# Config_Clock.net
KiCad netlist of a schematic drawn in Altium Designer
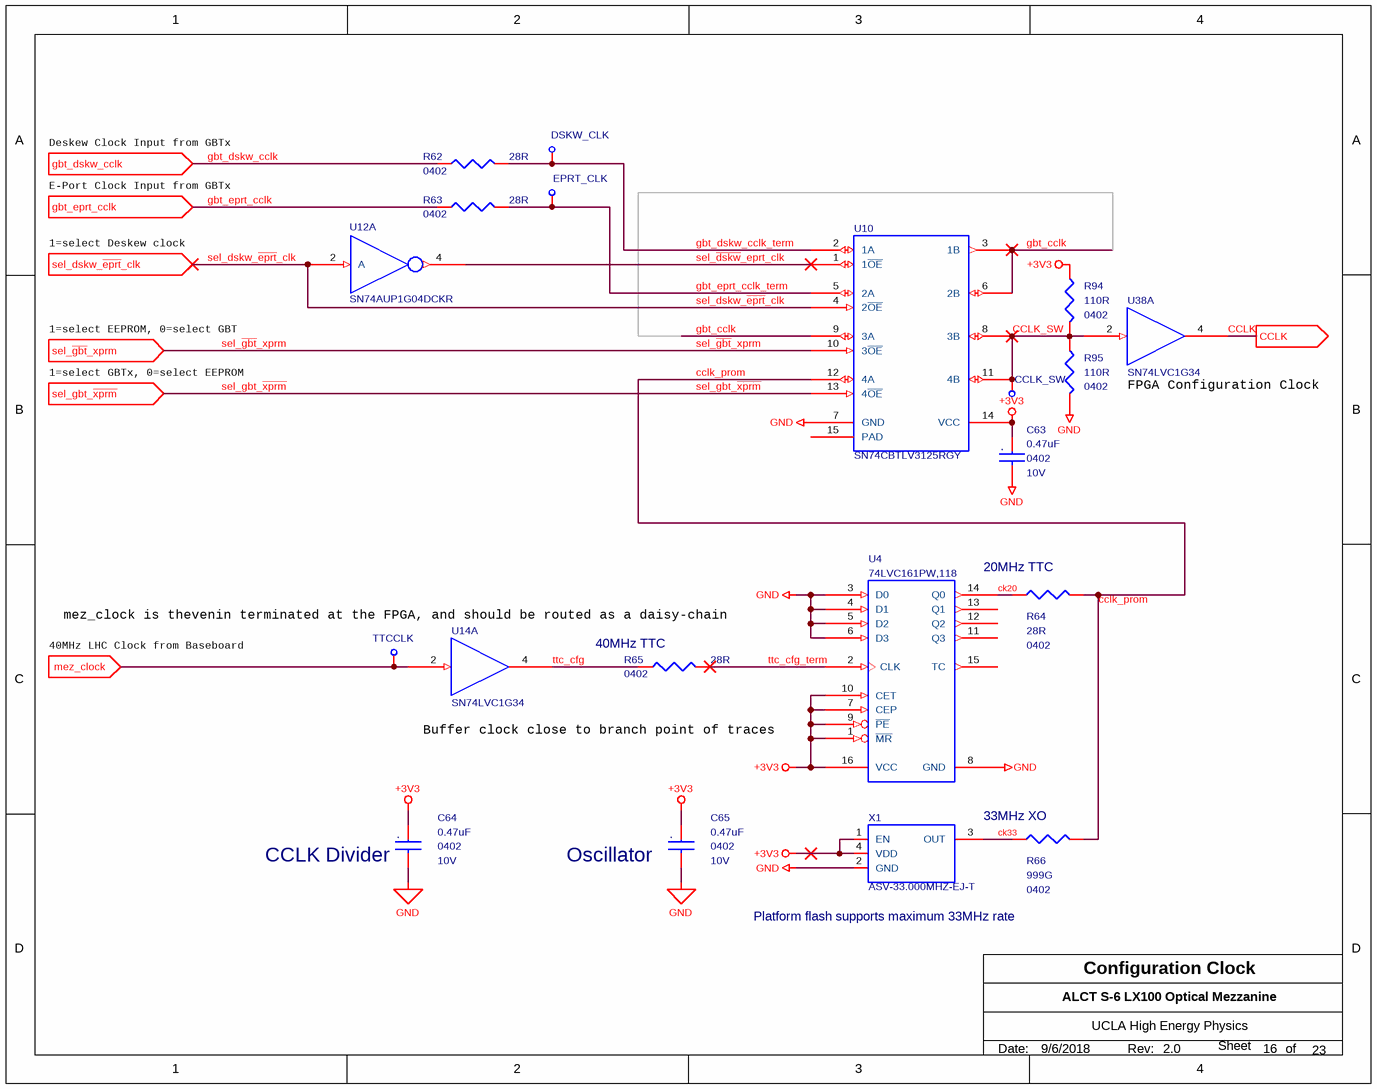
[diagram p0: Config_Clock.SchDoc]

(export (version "E")
  (design (tool "Eeschema 10.0.6"))
  (components
    (comp (ref "C63")
      (value "0.47uF")
      (footprint "MC_S6/SM/C_0402_IPC")
      (description "CAP CER 0.47UF 10V X5R 0402")
      (fields
        (field (name "MANUFACTURER") "Murata Electronics North America")
        (field (name "MANUFACTURER PART NUMBER") "GRM155R61A474KE15D")
        (field (name "VOLTAGE - RATED") "10V")
        (field (name "PACKAGE") "0402")
      )
      (libsource (lib "ALCT_MEZ_SPARTAN6_Library") (part "GRM155R61A474KE15D"))
    )
    (comp (ref "C64")
      (value "0.47uF")
      (footprint "MC_S6/SM/C_0402_IPC")
      (description "CAP CER 0.47UF 10V X5R 0402")
      (fields
        (field (name "MANUFACTURER") "Murata Electronics North America")
        (field (name "MANUFACTURER PART NUMBER") "GRM155R61A474KE15D")
        (field (name "PACKAGE") "0402")
        (field (name "VOLTAGE - RATED") "10V")
      )
      (libsource (lib "ALCT_MEZ_SPARTAN6_Library") (part "GRM155R61A474KE15D"))
    )
    (comp (ref "C65")
      (value "0.47uF")
      (footprint "MC_S6/SM/C_0402_IPC")
      (description "CAP CER 0.47UF 10V X5R 0402")
      (fields
        (field (name "MANUFACTURER") "Murata Electronics North America")
        (field (name "MANUFACTURER PART NUMBER") "GRM155R61A474KE15D")
        (field (name "PACKAGE") "0402")
        (field (name "VOLTAGE - RATED") "10V")
      )
      (libsource (lib "ALCT_MEZ_SPARTAN6_Library") (part "GRM155R61A474KE15D"))
    )
    (comp (ref "CCLK_SW")
      (value "Test Point Via")
      (footprint "MC_S6/TH/TPVIA")
      (libsource (lib "ALCT_MEZ_SPARTAN6_Library") (part "TPVIA"))
    )
    (comp (ref "DSKW_CLK")
      (value "Test Point Via")
      (footprint "MC_S6/TH/TPVIA")
      (libsource (lib "ALCT_MEZ_SPARTAN6_Library") (part "TPVIA"))
    )
    (comp (ref "EPRT_CLK")
      (value "Test Point Via")
      (footprint "MC_S6/TH/TPVIA")
      (libsource (lib "ALCT_MEZ_SPARTAN6_Library") (part "TPVIA"))
    )
    (comp (ref "R62")
      (value "28R")
      (footprint "MC_S6/SM/R_0402_IPC")
      (description "RES SMD 28 OHM 1% 1/10W 0402")
      (fields
        (field (name "TOLERANCE") "±1%")
        (field (name "MANUFACTURER") "Panasonic Electronic Components")
        (field (name "SUPPLIER DEVICE PACKAGE") "0402")
      )
      (libsource (lib "ALCT_MEZ_SPARTAN6_Library") (part "ERJ-2RKF28R0X"))
    )
    (comp (ref "R63")
      (value "28R")
      (footprint "MC_S6/SM/R_0402_IPC")
      (description "RES SMD 28 OHM 1% 1/10W 0402")
      (fields
        (field (name "TOLERANCE") "±1%")
        (field (name "MANUFACTURER") "Panasonic Electronic Components")
        (field (name "SUPPLIER DEVICE PACKAGE") "0402")
      )
      (libsource (lib "ALCT_MEZ_SPARTAN6_Library") (part "ERJ-2RKF28R0X"))
    )
    (comp (ref "R64")
      (value "28R")
      (footprint "MC_S6/SM/R_0402_IPC")
      (description "RES SMD 28 OHM 1% 1/10W 0402")
      (fields
        (field (name "TOLERANCE") "±1%")
        (field (name "MANUFACTURER") "Panasonic Electronic Components")
        (field (name "SUPPLIER DEVICE PACKAGE") "0402")
      )
      (libsource (lib "ALCT_MEZ_SPARTAN6_Library") (part "ERJ-2RKF28R0X"))
    )
    (comp (ref "R65")
      (value "28R")
      (footprint "MC_S6/SM/R_0402_IPC")
      (description "RES SMD 28 OHM 1% 1/10W 0402")
      (fields
        (field (name "TOLERANCE") "±1%")
        (field (name "MANUFACTURER") "Panasonic Electronic Components")
        (field (name "SUPPLIER DEVICE PACKAGE") "0402")
      )
      (libsource (lib "ALCT_MEZ_SPARTAN6_Library") (part "ERJ-2RKF28R0X"))
    )
    (comp (ref "R66")
      (value "999G")
      (footprint "MC_S6/SM/R_0402_IPC")
      (description "RES SMD 999G OHM 5% 1/16W 0402")
      (fields
        (field (name "SUPPLIER DEVICE PACKAGE") "0402")
        (field (name "MANUFACTURER PART NUMBER") "Do Not Place")
      )
      (libsource (lib "ALCT_MEZ_SPARTAN6_Library") (part "RES999G 0402"))
    )
    (comp (ref "R94")
      (value "110R")
      (footprint "MC_S6/SM/R_0402_IPC")
      (description "RES SMD 110 OHM 1% 1/10W 0402")
      (fields
        (field (name "MANUFACTURER") "Panasonic Electronic Components")
        (field (name "MANUFACTURER PART NUMBER") "ERJ-2RKF1100X")
        (field (name "SUPPLIER DEVICE PACKAGE") "0402")
      )
      (libsource (lib "ALCT_MEZ_SPARTAN6_Library") (part "ERJ-2RKF1100X"))
    )
    (comp (ref "R95")
      (value "110R")
      (footprint "MC_S6/SM/R_0402_IPC")
      (description "RES SMD 110 OHM 1% 1/10W 0402")
      (fields
        (field (name "MANUFACTURER") "Panasonic Electronic Components")
        (field (name "MANUFACTURER PART NUMBER") "ERJ-2RKF1100X")
        (field (name "SUPPLIER DEVICE PACKAGE") "0402")
      )
      (libsource (lib "ALCT_MEZ_SPARTAN6_Library") (part "ERJ-2RKF1100X"))
    )
    (comp (ref "TTCCLK")
      (value "Test Point Via")
      (footprint "MC_S6/TH/TPVIA")
      (libsource (lib "ALCT_MEZ_SPARTAN6_Library") (part "TPVIA"))
    )
    (comp (ref "U4")
      (value "74LVC161PW,118")
      (footprint "MC_S6/SM/TSSOP16")
      (description "IC SYNC 4BIT BIN COUNTER 16TSSOP")
      (fields (field (name "MANUFACTURER") "NXP USA Inc."))
      (libsource (lib "ALCT_MEZ_SPARTAN6_Library") (part "74LVC161PW"))
    )
    (comp (ref "U10")
      (value "SN74CBTLV3125RGY")
      (footprint "S-PVQFN-N14")
      (description "IC 4 BIT FET BUS SWITCH, QFN-14")
      (fields
        (field (name "MANUFACTURER") "Texas Instruments")
        (field (name "MANUFACTURER PART NUMBER") "SN74CBTLV3125RGYR")
      )
      (libsource (lib "ALCT_MEZ_SPARTAN6_Library") (part "SN74CBTLV3125RGY"))
    )
    (comp (ref "U12")
      (value "SN74AUP1G04DCKR")
      (footprint "MC_S6/SM/SOT_SC70_DCK5")
      (description "IC INVERTER LP 5TSSOP")
      (fields (field (name "MANUFACTURER") "Texas Instruments"))
      (libsource (lib "ALCT_MEZ_SPARTAN6_Library") (part "SN74AUP1G04DCKR"))
    )
    (comp (ref "U14")
      (value "SN74LVC1G34")
      (footprint "MC_S6/SM/SOT_553_DRL5")
      (description "IC BUFFER NON-INVERT SOT5")
      (fields
        (field (name "MANUFACTURER") "Texas Instruments")
        (field (name "MANUFACTURER PART NUMBER") "SN74LVC1G34DRLR")
      )
      (libsource (lib "ALCT_MEZ_SPARTAN6_Library") (part "SN74LVC1G34DRLR"))
    )
    (comp (ref "U38")
      (value "SN74LVC1G34")
      (footprint "MC_S6/SM/SOT_553_DRL5")
      (description "IC BUFFER NON-INVERT SOT5")
      (fields
        (field (name "MANUFACTURER") "Texas Instruments")
        (field (name "MANUFACTURER PART NUMBER") "SN74LVC1G34DRLR")
      )
      (libsource (lib "ALCT_MEZ_SPARTAN6_Library") (part "SN74LVC1G34DRLR"))
    )
    (comp (ref "X1")
      (value "ASV-33.000MHZ-EJ-T")
      (footprint "MC_S6/SM/XTAL-7x5.08")
      (description "XTAL, 33MHz, CMOS")
      (fields (field (name "MANUFACTURER") "Abracon LLC"))
      (libsource (lib "ALCT_MEZ_SPARTAN6_Library") (part "ASV-33.000MHZ-EJ-T"))
    )
  )
  (nets
    (net (code "1") (name "+3V3") (class "Default")
      (node (ref "C63") (pin "1") (pinfunction "1_1") (pintype "passive"))
      (node (ref "C64") (pin "1") (pinfunction "1_1") (pintype "passive"))
      (node (ref "C65") (pin "1") (pinfunction "1_1") (pintype "passive"))
      (node (ref "R94") (pin "1") (pinfunction "1_1") (pintype "passive"))
      (node (ref "U10") (pin "14") (pinfunction "VCC_14") (pintype "power_in"))
      (node (ref "U4") (pin "1") (pinfunction "~{MR}_1") (pintype "input"))
      (node (ref "U4") (pin "10") (pinfunction "CET_10") (pintype "input"))
      (node (ref "U4") (pin "16") (pinfunction "VCC_16") (pintype "power_in"))
      (node (ref "U4") (pin "7") (pinfunction "CEP_7") (pintype "input"))
      (node (ref "U4") (pin "9") (pinfunction "~{PE}_9") (pintype "input"))
      (node (ref "X1") (pin "1") (pinfunction "EN_1") (pintype "passive"))
      (node (ref "X1") (pin "4") (pinfunction "VDD_4") (pintype "passive"))
    )
    (net (code "2") (name "/CCLK") (class "Default")
      (node (ref "U38") (pin "4") (pinfunction "Y_4") (pintype "open_collector"))
    )
    (net (code "3") (name "/CCLK_SW") (class "Default")
      (node (ref "CCLK_SW") (pin "1") (pinfunction "In_1") (pintype "passive"))
      (node (ref "R94") (pin "2") (pinfunction "2_2") (pintype "passive"))
      (node (ref "R95") (pin "1") (pinfunction "1_1") (pintype "passive"))
      (node (ref "U10") (pin "11") (pinfunction "4B_11") (pintype "bidirectional"))
      (node (ref "U10") (pin "8") (pinfunction "3B_8") (pintype "bidirectional"))
      (node (ref "U38") (pin "2") (pinfunction "A_2") (pintype "input"))
    )
    (net (code "4") (name "/cclk_prom") (class "Default")
      (node (ref "R64") (pin "2") (pinfunction "2_2") (pintype "passive"))
      (node (ref "R66") (pin "2") (pinfunction "2_2") (pintype "passive"))
      (node (ref "U10") (pin "12") (pinfunction "4A_12") (pintype "bidirectional"))
    )
    (net (code "5") (name "/ck20") (class "Default")
      (node (ref "R64") (pin "1") (pinfunction "1_1") (pintype "passive"))
      (node (ref "U4") (pin "14") (pinfunction "Q0_14") (pintype "output"))
    )
    (net (code "6") (name "/ck33") (class "Default")
      (node (ref "R66") (pin "1") (pinfunction "1_1") (pintype "passive"))
      (node (ref "X1") (pin "3") (pinfunction "OUT_3") (pintype "passive"))
    )
    (net (code "7") (name "/gbt_cclk") (class "Default")
      (node (ref "U10") (pin "3") (pinfunction "1B_3") (pintype "output"))
      (node (ref "U10") (pin "6") (pinfunction "2B_6") (pintype "bidirectional"))
      (node (ref "U10") (pin "9") (pinfunction "3A_9") (pintype "bidirectional"))
    )
    (net (code "8") (name "/gbt_dskw_cclk") (class "Default")
      (node (ref "R62") (pin "1") (pinfunction "1_1") (pintype "passive"))
    )
    (net (code "9") (name "/gbt_dskw_cclk_term") (class "Default")
      (node (ref "DSKW_CLK") (pin "1") (pinfunction "In_1") (pintype "passive"))
      (node (ref "R62") (pin "2") (pinfunction "2_2") (pintype "passive"))
      (node (ref "U10") (pin "2") (pinfunction "1A_2") (pintype "bidirectional"))
    )
    (net (code "10") (name "/gbt_eprt_cclk") (class "Default")
      (node (ref "R63") (pin "1") (pinfunction "1_1") (pintype "passive"))
    )
    (net (code "11") (name "/gbt_eprt_cclk_term") (class "Default")
      (node (ref "EPRT_CLK") (pin "1") (pinfunction "In_1") (pintype "passive"))
      (node (ref "R63") (pin "2") (pinfunction "2_2") (pintype "passive"))
      (node (ref "U10") (pin "5") (pinfunction "2A_5") (pintype "bidirectional"))
    )
    (net (code "12") (name "/mez_clock") (class "Default")
      (node (ref "TTCCLK") (pin "1") (pinfunction "In_1") (pintype "passive"))
      (node (ref "U14") (pin "2") (pinfunction "A_2") (pintype "input"))
    )
    (net (code "13") (name "/sel_dskw_~{eprt}_clk") (class "Default")
      (node (ref "U10") (pin "4") (pinfunction "2~{OE}_4") (pintype "input"))
      (node (ref "U12") (pin "2") (pinfunction "A_2") (pintype "input"))
    )
    (net (code "14") (name "/sel_gbt_~{xprm}") (class "Default")
      (node (ref "U10") (pin "13") (pinfunction "4~{OE}_13") (pintype "input"))
    )
    (net (code "15") (name "/sel_~{dskw}_eprt_clk") (class "Default")
      (node (ref "U10") (pin "1") (pinfunction "1~{OE}_1") (pintype "bidirectional"))
      (node (ref "U12") (pin "4") (pinfunction "Y_4") (pintype "output"))
    )
    (net (code "16") (name "/sel_~{gbt}_xprm") (class "Default")
      (node (ref "U10") (pin "10") (pinfunction "3~{OE}_10") (pintype "input"))
    )
    (net (code "17") (name "/ttc_cfg") (class "Default")
      (node (ref "R65") (pin "1") (pinfunction "1_1") (pintype "passive"))
      (node (ref "U14") (pin "4") (pinfunction "Y_4") (pintype "open_collector"))
    )
    (net (code "18") (name "/ttc_cfg_term") (class "Default")
      (node (ref "R65") (pin "2") (pinfunction "2_2") (pintype "passive"))
      (node (ref "U4") (pin "2") (pinfunction "CLK_2") (pintype "input"))
    )
    (net (code "19") (name "GND") (class "Default")
      (node (ref "C63") (pin "2") (pinfunction "2_2") (pintype "passive"))
      (node (ref "C64") (pin "2") (pinfunction "2_2") (pintype "passive"))
      (node (ref "C65") (pin "2") (pinfunction "2_2") (pintype "passive"))
      (node (ref "R95") (pin "2") (pinfunction "2_2") (pintype "passive"))
      (node (ref "U10") (pin "7") (pinfunction "GND_7") (pintype "power_in"))
      (node (ref "U4") (pin "3") (pinfunction "D0_3") (pintype "input"))
      (node (ref "U4") (pin "4") (pinfunction "D1_4") (pintype "input"))
      (node (ref "U4") (pin "5") (pinfunction "D2_5") (pintype "input"))
      (node (ref "U4") (pin "6") (pinfunction "D3_6") (pintype "input"))
      (node (ref "U4") (pin "8") (pinfunction "GND_8") (pintype "power_in"))
      (node (ref "X1") (pin "2") (pinfunction "GND_2") (pintype "passive"))
    )
    (net (code "20") (name "unconnected-(U4-Q1-Pad13)") (class "Default")
      (node (ref "U4") (pin "13") (pinfunction "Q1_13") (pintype "output"))
    )
    (net (code "21") (name "unconnected-(U4-Q2-Pad12)") (class "Default")
      (node (ref "U4") (pin "12") (pinfunction "Q2_12") (pintype "output"))
    )
    (net (code "22") (name "unconnected-(U4-Q3-Pad11)") (class "Default")
      (node (ref "U4") (pin "11") (pinfunction "Q3_11") (pintype "output"))
    )
    (net (code "23") (name "unconnected-(U4-TC-Pad15)") (class "Default")
      (node (ref "U4") (pin "15") (pinfunction "TC_15") (pintype "output"))
    )
    (net (code "24") (name "unconnected-(U10-PAD-Pad15)") (class "Default")
      (node (ref "U10") (pin "15") (pinfunction "PAD_15") (pintype "power_in"))
    )
  )
)
